# A3210.net
KiCad netlist of a schematic drawn in Altium Designer
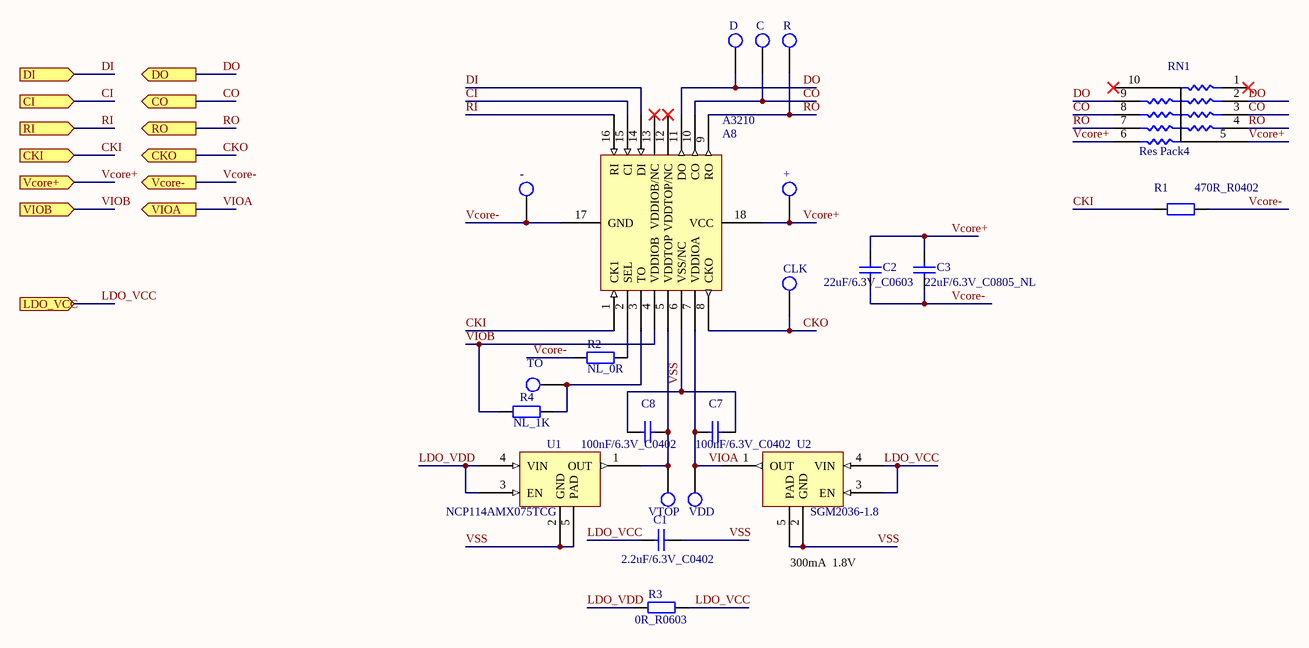
[diagram p0: A3210.SchDoc]

(export (version "E")
  (design (tool "Eeschema 10.0.6"))
  (components
    (comp (ref "+")
      (value "Socket")
      (footprint "tp28")
      (description "TP")
      (fields (field (name "PUBLISHER") "Altium Limited"))
      (libsource (lib "A7.1") (part "Socket"))
    )
    (comp (ref "-")
      (value "Socket")
      (footprint "tp28")
      (description "TP")
      (fields (field (name "PUBLISHER") "Altium Limited"))
      (libsource (lib "A7.1") (part "Socket"))
    )
    (comp (ref "A8") (value "A3210") (footprint "DFN-A8-007") (libsource (lib "A3210") (part "Component_1")))
    (comp (ref "C")
      (value "Socket")
      (footprint "tp28")
      (description "TP")
      (fields (field (name "PUBLISHER") "Altium Limited"))
      (libsource (lib "A7.1") (part "Socket"))
    )
    (comp (ref "C1")
      (value "2.2uF/6.3V_C0402")
      (footprint "c0402")
      (description "Capacitor")
      (fields (field (name "Comment") "Cap") (field (name "PUBLISHER") "Altium Limited"))
      (libsource (lib "Miscellaneous Devices") (part "Cap"))
    )
    (comp (ref "C2")
      (value "22uF/6.3V_C0603")
      (footprint "c0603")
      (description "Capacitor")
      (fields (field (name "Comment") "Cap") (field (name "PUBLISHER") "Altium Limited"))
      (libsource (lib "Miscellaneous Devices") (part "Cap"))
    )
    (comp (ref "C3")
      (value "22uF/6.3V_C0805_NL")
      (footprint "c0805")
      (description "Capacitor")
      (fields (field (name "Comment") "Cap") (field (name "PUBLISHER") "Altium Limited"))
      (libsource (lib "Miscellaneous Devices") (part "Cap"))
    )
    (comp (ref "C7")
      (value "100nF/6.3V_C0402")
      (footprint "c0402")
      (description "Capacitor")
      (fields (field (name "Comment") "Cap") (field (name "PUBLISHER") "Altium Limited"))
      (libsource (lib "Miscellaneous Devices") (part "Cap"))
    )
    (comp (ref "C8")
      (value "100nF/6.3V_C0402")
      (footprint "c0402")
      (description "Capacitor")
      (fields (field (name "Comment") "Cap") (field (name "PUBLISHER") "Altium Limited"))
      (libsource (lib "Miscellaneous Devices") (part "Cap"))
    )
    (comp (ref "CLK")
      (value "Socket")
      (footprint "tp28")
      (description "TP")
      (fields (field (name "PUBLISHER") "Altium Limited"))
      (libsource (lib "A7.1") (part "Socket"))
    )
    (comp (ref "D")
      (value "Socket")
      (footprint "tp28")
      (description "TP")
      (fields (field (name "PUBLISHER") "Altium Limited"))
      (libsource (lib "A7.1") (part "Socket"))
    )
    (comp (ref "R")
      (value "Socket")
      (footprint "tp28")
      (description "TP")
      (fields (field (name "PUBLISHER") "Altium Limited"))
      (libsource (lib "A7.1") (part "Socket"))
    )
    (comp (ref "R1")
      (value "470R_R0402")
      (footprint "r0402")
      (description "Resistor")
      (fields (field (name "Comment") "Res2") (field (name "PUBLISHER") "Altium Limited"))
      (libsource (lib "") (part "Res2_1"))
    )
    (comp (ref "R2")
      (value "NL_0R")
      (footprint "R0603")
      (description "Resistor")
      (fields (field (name "Comment") "Res2") (field (name "PUBLISHER") "Altium Limited"))
      (libsource (lib "") (part "Res2_1"))
    )
    (comp (ref "R3")
      (value "0R_R0603")
      (footprint "R0603")
      (description "Resistor")
      (fields (field (name "Comment") "Res2") (field (name "PUBLISHER") "Altium Limited"))
      (libsource (lib "") (part "Res2_1"))
    )
    (comp (ref "R4")
      (value "NL_1K")
      (footprint "R0402")
      (description "Resistor")
      (fields (field (name "Comment") "Res2") (field (name "PUBLISHER") "Altium Limited"))
      (libsource (lib "Miscellaneous Devices") (part "Res2"))
    )
    (comp (ref "RN1")
      (value "Res Pack4")
      (footprint "RN0402-8-a")
      (description "YC158")
      (fields (field (name "PUBLISHER") "Altium Limited"))
      (libsource (lib "A7-20x") (part "Res Pack4"))
    )
    (comp (ref "TO")
      (value "Socket")
      (footprint "tp28")
      (description "TP")
      (fields (field (name "PUBLISHER") "Altium Limited"))
      (libsource (lib "A7.1") (part "Socket"))
    )
    (comp (ref "U1")
      (value "NCP114AMX075TCG")
      (footprint "DFN4-065-0101-006-N")
      (libsource (lib "NCP114AMX075TCG") (part "Component_1"))
    )
    (comp (ref "U2")
      (value "SGM2036-1.8")
      (footprint "DFN4-065-0101-006-N")
      (libsource (lib "SGM2036-1.8") (part "Component_1"))
    )
    (comp (ref "VDD")
      (value "Socket")
      (footprint "tp28")
      (description "TP")
      (fields (field (name "PUBLISHER") "Altium Limited"))
      (libsource (lib "A7.1") (part "Socket"))
    )
    (comp (ref "VTOP")
      (value "Socket")
      (footprint "tp28")
      (description "TP")
      (fields (field (name "PUBLISHER") "Altium Limited"))
      (libsource (lib "A7.1") (part "Socket"))
    )
  )
  (nets
    (net (code "1") (name "/CI") (class "Default")
      (node (ref "A8") (pin "15") (pinfunction "CI_15") (pintype "input"))
    )
    (net (code "2") (name "/CKI") (class "Default")
      (node (ref "A8") (pin "1") (pinfunction "CK1_1") (pintype "input"))
      (node (ref "R1") (pin "2") (pinfunction "2_2") (pintype "passive"))
    )
    (net (code "3") (name "/CKO") (class "Default")
      (node (ref "A8") (pin "8") (pinfunction "CKO_8") (pintype "output"))
      (node (ref "CLK") (pin "1") (pinfunction "1_1") (pintype "passive"))
    )
    (net (code "4") (name "/CO") (class "Default")
      (node (ref "A8") (pin "10") (pinfunction "CO_10") (pintype "output"))
      (node (ref "C") (pin "1") (pinfunction "1_1") (pintype "passive"))
      (node (ref "RN1") (pin "3") (pinfunction "3_3") (pintype "passive"))
      (node (ref "RN1") (pin "8") (pinfunction "8_8") (pintype "passive"))
    )
    (net (code "5") (name "/DI") (class "Default")
      (node (ref "A8") (pin "14") (pinfunction "DI_14") (pintype "input"))
    )
    (net (code "6") (name "/DO") (class "Default")
      (node (ref "A8") (pin "11") (pinfunction "DO_11") (pintype "output"))
      (node (ref "D") (pin "1") (pinfunction "1_1") (pintype "passive"))
      (node (ref "RN1") (pin "2") (pinfunction "2_2") (pintype "passive"))
      (node (ref "RN1") (pin "9") (pinfunction "9_9") (pintype "passive"))
    )
    (net (code "7") (name "/LDO_VCC") (class "Default")
      (node (ref "C1") (pin "1") (pinfunction "1_1") (pintype "passive"))
      (node (ref "R3") (pin "1") (pinfunction "1_1") (pintype "passive"))
      (node (ref "U2") (pin "3") (pinfunction "EN_3") (pintype "input"))
      (node (ref "U2") (pin "4") (pinfunction "VIN_4") (pintype "input"))
    )
    (net (code "8") (name "/LDO_VDD") (class "Default")
      (node (ref "R3") (pin "2") (pinfunction "2_2") (pintype "passive"))
      (node (ref "U1") (pin "3") (pinfunction "EN_3") (pintype "input"))
      (node (ref "U1") (pin "4") (pinfunction "VIN_4") (pintype "input"))
    )
    (net (code "9") (name "/RI") (class "Default")
      (node (ref "A8") (pin "16") (pinfunction "RI_16") (pintype "input"))
    )
    (net (code "10") (name "/RO") (class "Default")
      (node (ref "A8") (pin "9") (pinfunction "RO_9") (pintype "output"))
      (node (ref "R") (pin "1") (pinfunction "1_1") (pintype "passive"))
      (node (ref "RN1") (pin "4") (pinfunction "4_4") (pintype "passive"))
      (node (ref "RN1") (pin "7") (pinfunction "7_7") (pintype "passive"))
    )
    (net (code "11") (name "/VIOA") (class "Default")
      (node (ref "A8") (pin "7") (pinfunction "VDDIOA_7") (pintype "power_in"))
      (node (ref "C7") (pin "1") (pinfunction "1_1") (pintype "passive"))
      (node (ref "U2") (pin "1") (pinfunction "OUT_1") (pintype "output"))
      (node (ref "VDD") (pin "1") (pinfunction "1_1") (pintype "passive"))
    )
    (net (code "12") (name "/VIOB") (class "Default")
      (node (ref "A8") (pin "4") (pinfunction "VDDIOB_4") (pintype "power_in"))
      (node (ref "R4") (pin "1") (pinfunction "1_1") (pintype "passive"))
    )
    (net (code "13") (name "/VSS") (class "Default")
      (node (ref "A8") (pin "6") (pinfunction "VSS/NC_6") (pintype "power_in"))
      (node (ref "C1") (pin "2") (pinfunction "2_2") (pintype "passive"))
      (node (ref "C7") (pin "2") (pinfunction "2_2") (pintype "passive"))
      (node (ref "C8") (pin "1") (pinfunction "1_1") (pintype "passive"))
      (node (ref "U1") (pin "2") (pinfunction "GND_2") (pintype "passive"))
      (node (ref "U1") (pin "5") (pinfunction "PAD_5") (pintype "power_in"))
      (node (ref "U2") (pin "2") (pinfunction "GND_2") (pintype "power_in"))
      (node (ref "U2") (pin "5") (pinfunction "PAD_5") (pintype "power_in"))
    )
    (net (code "14") (name "/Vcore+") (class "Default")
      (node (ref "+") (pin "1") (pinfunction "1_1") (pintype "passive"))
      (node (ref "A8") (pin "18") (pinfunction "VCC_18") (pintype "power_in"))
      (node (ref "C2") (pin "1") (pinfunction "1_1") (pintype "passive"))
      (node (ref "C3") (pin "1") (pinfunction "1_1") (pintype "passive"))
      (node (ref "RN1") (pin "5") (pinfunction "5_5") (pintype "passive"))
      (node (ref "RN1") (pin "6") (pinfunction "6_6") (pintype "passive"))
    )
    (net (code "15") (name "/Vcore-") (class "Default")
      (node (ref "-") (pin "1") (pinfunction "1_1") (pintype "passive"))
      (node (ref "A8") (pin "17") (pinfunction "GND_17") (pintype "power_in"))
      (node (ref "C2") (pin "2") (pinfunction "2_2") (pintype "passive"))
      (node (ref "C3") (pin "2") (pinfunction "2_2") (pintype "passive"))
      (node (ref "R1") (pin "1") (pinfunction "1_1") (pintype "passive"))
      (node (ref "R2") (pin "2") (pinfunction "2_2") (pintype "passive"))
    )
    (net (code "16") (name "Net-(A8-SEL)") (class "Default")
      (node (ref "A8") (pin "2") (pinfunction "SEL_2") (pintype "passive"))
      (node (ref "R2") (pin "1") (pinfunction "1_1") (pintype "passive"))
    )
    (net (code "17") (name "Net-(A8-TO)") (class "Default")
      (node (ref "A8") (pin "3") (pinfunction "TO_3") (pintype "passive"))
      (node (ref "R4") (pin "2") (pinfunction "2_2") (pintype "passive"))
      (node (ref "TO") (pin "1") (pinfunction "1_1") (pintype "passive"))
    )
    (net (code "18") (name "Net-(A8-VDDTOP)") (class "Default")
      (node (ref "A8") (pin "5") (pinfunction "VDDTOP_5") (pintype "power_in"))
      (node (ref "C8") (pin "2") (pinfunction "2_2") (pintype "passive"))
      (node (ref "U1") (pin "1") (pinfunction "OUT_1") (pintype "output"))
      (node (ref "VTOP") (pin "1") (pinfunction "1_1") (pintype "passive"))
    )
    (net (code "19") (name "unconnected-(A8-VDDIOB{slash}NC-Pad13)") (class "Default")
      (node (ref "A8") (pin "13") (pinfunction "VDDIOB/NC_13") (pintype "passive+no_connect"))
    )
    (net (code "20") (name "unconnected-(A8-VDDTOP{slash}NC-Pad12)") (class "Default")
      (node (ref "A8") (pin "12") (pinfunction "VDDTOP/NC_12") (pintype "power_in+no_connect"))
    )
    (net (code "21") (name "unconnected-(RN1-Pad1)") (class "Default")
      (node (ref "RN1") (pin "1") (pinfunction "1_1") (pintype "passive+no_connect"))
    )
    (net (code "22") (name "unconnected-(RN1-Pad10)") (class "Default")
      (node (ref "RN1") (pin "10") (pinfunction "10_10") (pintype "passive+no_connect"))
    )
  )
)
